# Power_Supply.net
KiCad netlist of a schematic drawn in Altium Designer
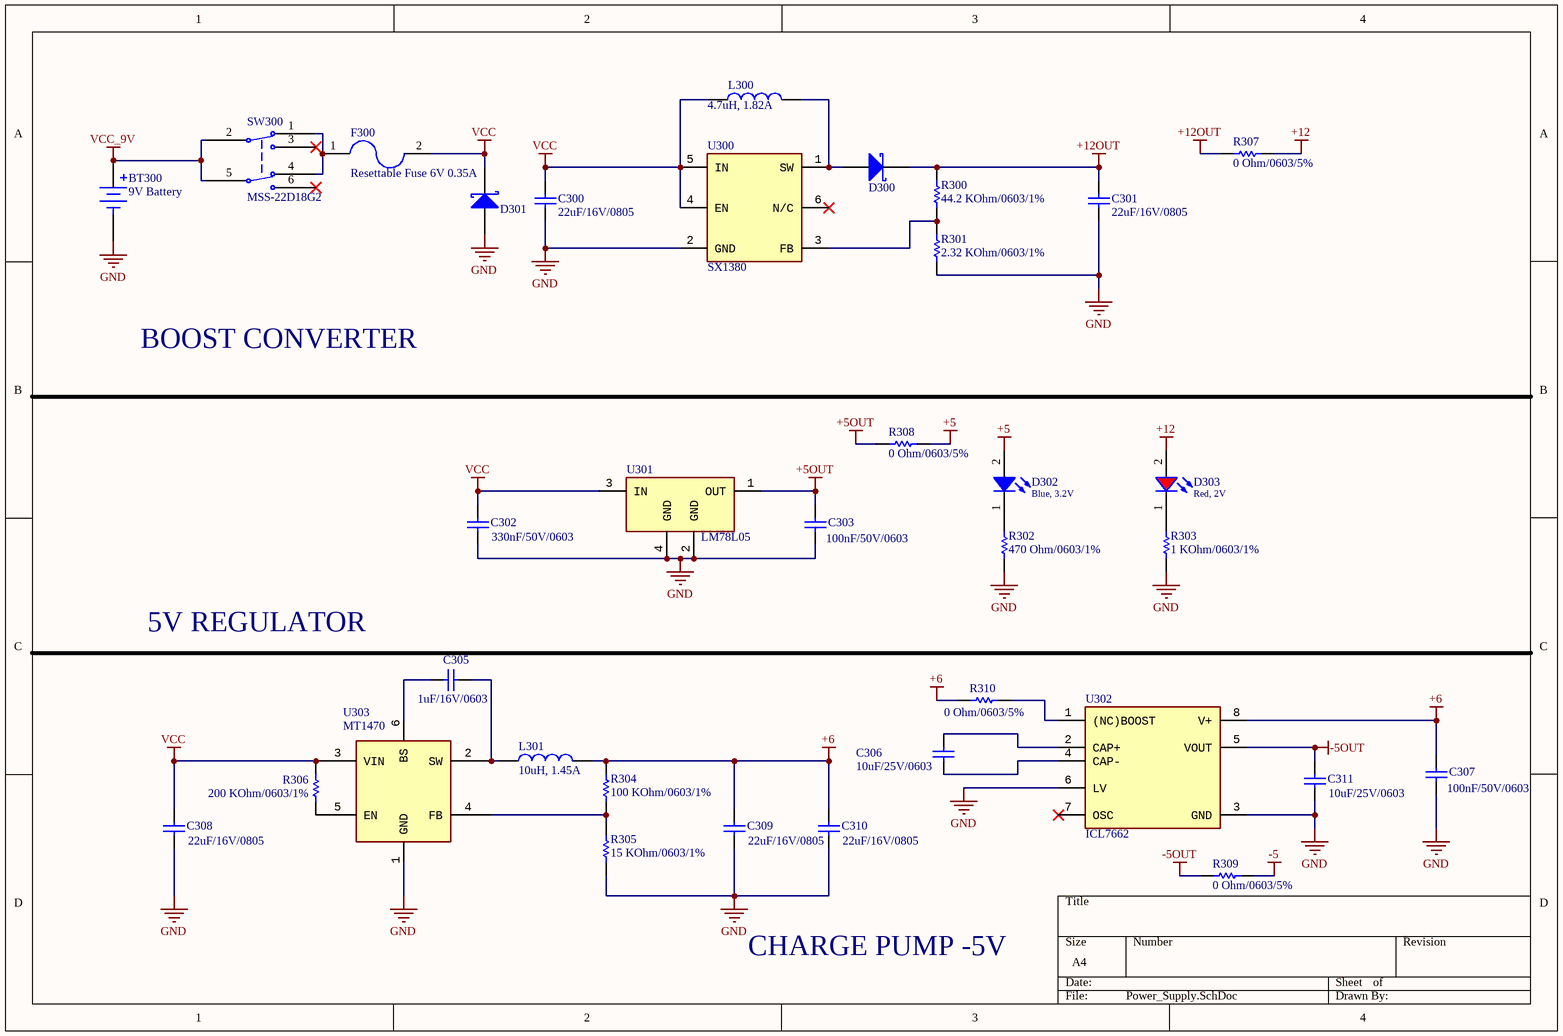
[diagram p0: Power_Supply.SchDoc]

(export (version "E")
  (design (tool "Eeschema 10.0.6"))
  (components
    (comp (ref "BT300")
      (value "9V Battery")
      (footprint "BAT_BC9VPC")
      (description "Battery Holder 1 Cells 9V Size Plastic Tray")
      (fields (field (name "MF") "MPD (Memory Protection Devices)") (field (name "MP") "BC9VPC"))
      (libsource (lib "Giang's Libs") (part "BC9VPC"))
    )
    (comp (ref "C300")
      (value "22uF/16V/0805")
      (footprint "CAP-SM-0805")
      (description "Capacitor")
      (fields (field (name "Comment") "Cap Non-Pol SMD"))
      (libsource (lib "PIF_Library") (part "Cap Non-Pol SMD"))
    )
    (comp (ref "C301")
      (value "22uF/16V/0805")
      (footprint "CAP-SM-0805")
      (description "Capacitor")
      (fields (field (name "Comment") "Cap Non-Pol SMD"))
      (libsource (lib "PIF_Library") (part "Cap Non-Pol SMD"))
    )
    (comp (ref "C302")
      (value "330nF/50V/0603")
      (footprint "WCAP-CSGP_0603_H=0.8mm_Reflow")
      (description "WCAP-CSGP Multilayer Ceramic Chip Capacitor, General Purpose, size 0603, X7R, 330nF, 50V")
      (fields
        (field (name "MANUFACTURER PART NUMBER") "885012206121")
        (field (name "MANUFACTURER") "Wurth Elektronik")
      )
      (libsource (lib "Altium_WCAP-CSGP (rev20a)") (part "885012206121"))
    )
    (comp (ref "C303")
      (value "100nF/50V/0603")
      (footprint "WCAP-CSGP_0603_H=0.8mm_Reflow")
      (description "WCAP-CSGP Multilayer Ceramic Chip Capacitor, General Purpose, size 0603, X7R, 100nF, 25V")
      (fields
        (field (name "MANUFACTURER PART NUMBER") "885012206071")
        (field (name "MANUFACTURER") "Wurth Elektronik")
      )
      (libsource (lib "Altium_WCAP-CSGP (rev20a)") (part "885012206071"))
    )
    (comp (ref "C305")
      (value "1uF/16V/0603")
      (footprint "WCAP-CSGP_0603_H=0.8mm_Reflow")
      (description "WCAP-CSGP Multilayer Ceramic Chip Capacitor, General Purpose, size 0603, X5R, 1uF, 16V")
      (fields
        (field (name "MANUFACTURER PART NUMBER") "885012106017")
        (field (name "MANUFACTURER") "Wurth Elektronik")
      )
      (libsource (lib "Altium_WCAP-CSGP (rev20a)") (part "885012106017"))
    )
    (comp (ref "C306")
      (value "10uF/25V/0603")
      (footprint "WCAP-CSGP_0603_H=0.8mm_Reflow")
      (description "WCAP-CSGP Multilayer Ceramic Chip Capacitor, General Purpose, size 0603, X5R, 10uF, 6.3V")
      (fields
        (field (name "MANUFACTURER PART NUMBER") "885012106006")
        (field (name "MANUFACTURER") "Wurth Elektronik")
      )
      (libsource (lib "Altium_WCAP-CSGP (rev20a)") (part "885012106006"))
    )
    (comp (ref "C307")
      (value "100nF/50V/0603")
      (footprint "WCAP-CSGP_0603_H=0.8mm_Reflow")
      (description "WCAP-CSGP Multilayer Ceramic Chip Capacitor, General Purpose, size 0603, X7R, 100nF, 25V")
      (fields
        (field (name "MANUFACTURER PART NUMBER") "885012206071")
        (field (name "MANUFACTURER") "Wurth Elektronik")
      )
      (libsource (lib "Altium_WCAP-CSGP (rev20a)") (part "885012206071"))
    )
    (comp (ref "C308")
      (value "22uF/16V/0805")
      (footprint "WCAP-CSGP_0805_H=1.25mm")
      (description "WCAP-CSGP Multilayer Ceramic Chip Capacitor, General Purpose, size 0805, X5R, 22uF, 10V")
      (fields
        (field (name "MANUFACTURER PART NUMBER") "885012107011")
        (field (name "MANUFACTURER") "Wurth Elektronik")
      )
      (libsource (lib "Altium_WCAP-CSGP (rev20a)") (part "885012107011"))
    )
    (comp (ref "C309")
      (value "22uF/16V/0805")
      (footprint "WCAP-CSGP_0805_H=1.25mm")
      (description "WCAP-CSGP Multilayer Ceramic Chip Capacitor, General Purpose, size 0805, X5R, 22uF, 10V")
      (fields
        (field (name "MANUFACTURER PART NUMBER") "885012107011")
        (field (name "MANUFACTURER") "Wurth Elektronik")
      )
      (libsource (lib "Altium_WCAP-CSGP (rev20a)") (part "885012107011"))
    )
    (comp (ref "C310")
      (value "22uF/16V/0805")
      (footprint "WCAP-CSGP_0805_H=1.25mm")
      (description "WCAP-CSGP Multilayer Ceramic Chip Capacitor, General Purpose, size 0805, X5R, 22uF, 10V")
      (fields
        (field (name "MANUFACTURER PART NUMBER") "885012107011")
        (field (name "MANUFACTURER") "Wurth Elektronik")
      )
      (libsource (lib "Altium_WCAP-CSGP (rev20a)") (part "885012107011"))
    )
    (comp (ref "C311")
      (value "10uF/25V/0603")
      (footprint "WCAP-CSGP_0603_H=0.8mm_Reflow")
      (description "WCAP-CSGP Multilayer Ceramic Chip Capacitor, General Purpose, size 0603, X5R, 10uF, 6.3V")
      (fields
        (field (name "MANUFACTURER PART NUMBER") "885012106006")
        (field (name "MANUFACTURER") "Wurth Elektronik")
      )
      (libsource (lib "Altium_WCAP-CSGP (rev20a)") (part "885012106006"))
    )
    (comp (ref "D300")
      (value "D Schottky")
      (footprint "SS34")
      (description "Schottky Diode")
      (fields (field (name "PUBLISHER") "Altium Limited"))
      (libsource (lib "PIF_Library") (part "D Schottky"))
    )
    (comp (ref "D301")
      (value "D Schottky")
      (footprint "SS34")
      (description "Schottky Diode")
      (fields (field (name "PUBLISHER") "Altium Limited"))
      (libsource (lib "PIF_Library") (part "D Schottky"))
    )
    (comp (ref "D302")
      (value "Blue, 3.2V")
      (footprint "WL-SMCW_0603_H=0.7mm")
      (description "WL-SMCW SMT Mono-color Chip LED Waterclear, size 0603, Blue, 3.2V, 140deg")
      (fields (field (name "PART NUMBER") "150060BS75000") (field (name "PUBLISHER") "Wurth Elektronik"))
      (libsource (lib "Altium_WL-SMCW (rev20a)") (part "150060BS75000"))
    )
    (comp (ref "D303")
      (value "Red, 2V")
      (footprint "WL-SMCW_0603_H=0.7mm")
      (description "WL-SMCW SMT Mono-color Chip LED Waterclear, size 0603, Red, 2V, 140deg")
      (fields (field (name "PART NUMBER") "150060RS75000") (field (name "PUBLISHER") "Wurth Elektronik"))
      (libsource (lib "Altium_WL-SMCW (rev20a)") (part "150060RS75000"))
    )
    (comp (ref "F300")
      (value "Resettable Fuse 6V 0.35A")
      (footprint "FUSE1206")
      (description "Polymeric PTC Resettable Fuse 6V 350mA Ih Surface Mount 1206 _3216 Metric_, Concave")
      (fields (field (name "MF") "Littelfuse Inc.") (field (name "MP") "1206L035YR"))
      (libsource (lib "Giang's Libs") (part "RESETTABLE FUSE 1206"))
    )
    (comp (ref "L300")
      (value "4.7uH, 1.82A")
      (footprint "WE-PD2A_4532")
      (description "WE-PD2A SMT Power Inductor, size 4532, 4.7uH, 1.82A")
      (fields
        (field (name "MANUFACTURER PART NUMBER") "784773047")
        (field (name "MANUFACTURER") "Wurth Elektronik")
      )
      (libsource (lib "Altium_WE-PD2A (rev20a)") (part "784773047"))
    )
    (comp (ref "L301")
      (value "10uH, 1.45A")
      (footprint "WE-PD2A_4532")
      (description "WE-PD2A SMT Power Inductor, size 4532, 10uH, 1.45A")
      (fields
        (field (name "MANUFACTURER PART NUMBER") "78477310")
        (field (name "MANUFACTURER") "Wurth Elektronik")
      )
      (libsource (lib "Altium_WE-PD2A (rev20a)") (part "78477310"))
    )
    (comp (ref "R300")
      (value "44.2 KOhm/0603/1%")
      (footprint "R0603")
      (description "Code (4422, 63C), 1/10W 1%")
      (fields (field (name "Comment") "Resistor 44.2 KOhm 0603 1%"))
      (libsource (lib "Giang_Resistor") (part "Resistor 44.2 KOhm 0603 1%"))
    )
    (comp (ref "R301")
      (value "2.32 KOhm/0603/1%")
      (footprint "R0603")
      (description "Code (2321, 36B), 1/10W")
      (fields (field (name "Comment") "Resistor 2.32 KOhm 0603 1%"))
      (libsource (lib "Giang_Resistor") (part "Resistor 2.32 KOhm 0603 1%"))
    )
    (comp (ref "R302")
      (value "470 Ohm/0603/1%")
      (footprint "R0603")
      (description "Code 471, 1/10W")
      (fields (field (name "Comment") "Resistor 470 Ohm 0603 1%"))
      (libsource (lib "Giang_Resistor") (part "Resistor 470 Ohm 0603 1%"))
    )
    (comp (ref "R303")
      (value "1 KOhm/0603/1%")
      (footprint "R0603")
      (description "Code 102, 1/10W")
      (fields (field (name "Comment") "Resistor 1 KOhm 0603 1%"))
      (libsource (lib "Giang_Resistor") (part "Resistor 1 KOhm 0603 1%"))
    )
    (comp (ref "R304")
      (value "100 KOhm/0603/1%")
      (footprint "R0603")
      (description "Code 104, 1/10W")
      (fields (field (name "Comment") "Resistor 100 KOhm 0603 1%"))
      (libsource (lib "Giang_Resistor") (part "Resistor 100 KOhm 0603 1%"))
    )
    (comp (ref "R305")
      (value "15 KOhm/0603/1%")
      (footprint "R0603")
      (description "Code 153, 1/10W")
      (fields (field (name "Comment") "Resistor 15 KOhm 0603 1%"))
      (libsource (lib "Giang_Resistor") (part "Resistor 15 KOhm 0603 1%"))
    )
    (comp (ref "R306")
      (value "200 KOhm/0603/1%")
      (footprint "R0603")
      (description "Code 2003, 1/10W")
      (fields (field (name "Comment") "Resistor 200 KOhm 0603 5%"))
      (libsource (lib "Giang_Resistor") (part "Resistor 200 KOhm 0603 5%"))
    )
    (comp (ref "R307")
      (value "0 Ohm/0603/5%")
      (footprint "R0603")
      (description "Code 0R, 1/10W")
      (fields (field (name "Comment") "Resistor 0 Ohm 0603 5%"))
      (libsource (lib "Giang_Resistor") (part "Resistor 0 Ohm 0603 5%"))
    )
    (comp (ref "R308")
      (value "0 Ohm/0603/5%")
      (footprint "R0603")
      (description "Code 0R, 1/10W")
      (fields (field (name "Comment") "Resistor 0 Ohm 0603 5%"))
      (libsource (lib "Giang_Resistor") (part "Resistor 0 Ohm 0603 5%"))
    )
    (comp (ref "R309")
      (value "0 Ohm/0603/5%")
      (footprint "R0603")
      (description "Code 0R, 1/10W")
      (fields (field (name "Comment") "Resistor 0 Ohm 0603 5%"))
      (libsource (lib "Giang_Resistor") (part "Resistor 0 Ohm 0603 5%"))
    )
    (comp (ref "R310")
      (value "0 Ohm/0603/5%")
      (footprint "R0603")
      (description "Code 0R, 1/10W")
      (fields (field (name "Comment") "Resistor 0 Ohm 0603 5%"))
      (libsource (lib "Giang_Resistor") (part "Resistor 0 Ohm 0603 5%"))
    )
    (comp (ref "SW300")
      (value "MSS-22D18G2")
      (footprint "MSS-22D18G2")
      (description "Slide Switch")
      (libsource (lib "Giang's Libs") (part "Slide Switch"))
    )
    (comp (ref "U300")
      (value "SX1380")
      (footprint "SOT-23-6")
      (description "High Efficiency 1.2MHz 2A Step Up Converter")
      (fields (field (name "MF") "Semtech Corporation") (field (name "MP") "SX1308"))
      (libsource (lib "Giang's Libs") (part "SX1308"))
    )
    (comp (ref "U301")
      (value "LM78L05")
      (footprint "SOT-89")
      (description "IC REG LINEAR 5V 100MA SOT89-3")
      (fields (field (name "MP") "78L05") (field (name "MF") "Hottech Co"))
      (libsource (lib "Giang's Libs") (part "78L05"))
    )
    (comp (ref "U302")
      (value "ICL7662")
      (footprint "SOIC-8")
      (description "CMOS, Voltage Converters")
      (fields (field (name "MP") "ICL7662EBA+") (field (name "MF") "Analog Devices"))
      (libsource (lib "Giang's Libs") (part "ICL7662EBA+"))
    )
    (comp (ref "U303")
      (value "MT1470")
      (footprint "SOT-23-6")
      (description "2A, 4.5 - 18V Input, 500kHz Synchronous Step-Down Converter")
      (libsource (lib "Giang's Libs") (part "MT1470"))
    )
  )
  (nets
    (net (code "1") (name "+5") (class "Default")
      (node (ref "D302") (pin "2") (pinfunction "A_2") (pintype "passive"))
      (node (ref "R308") (pin "2") (pinfunction "2_2") (pintype "passive"))
    )
    (net (code "2") (name "+5OUT") (class "Default")
      (node (ref "C303") (pin "1") (pinfunction "1_1") (pintype "passive"))
      (node (ref "R308") (pin "1") (pinfunction "1_1") (pintype "passive"))
      (node (ref "U301") (pin "1") (pinfunction "OUT_1") (pintype "power_in"))
    )
    (net (code "3") (name "+6") (class "Default")
      (node (ref "C307") (pin "1") (pinfunction "1_1") (pintype "passive"))
      (node (ref "C309") (pin "2") (pinfunction "2_2") (pintype "passive"))
      (node (ref "C310") (pin "2") (pinfunction "2_2") (pintype "passive"))
      (node (ref "L301") (pin "2") (pinfunction "2_2") (pintype "passive"))
      (node (ref "R304") (pin "2") (pinfunction "2_2") (pintype "passive"))
      (node (ref "R310") (pin "1") (pinfunction "1_1") (pintype "passive"))
      (node (ref "U302") (pin "8") (pinfunction "V+_8") (pintype "passive"))
    )
    (net (code "4") (name "+12") (class "Default")
      (node (ref "D303") (pin "2") (pinfunction "A_2") (pintype "passive"))
      (node (ref "R307") (pin "2") (pinfunction "2_2") (pintype "passive"))
    )
    (net (code "5") (name "+12OUT") (class "Default")
      (node (ref "C301") (pin "2") (pinfunction "2_2") (pintype "passive"))
      (node (ref "D300") (pin "2") (pinfunction "K_2") (pintype "passive"))
      (node (ref "R300") (pin "2") (pinfunction "2_2") (pintype "passive"))
      (node (ref "R307") (pin "1") (pinfunction "1_1") (pintype "passive"))
    )
    (net (code "6") (name "-5") (class "Default")
      (node (ref "R309") (pin "2") (pinfunction "2_2") (pintype "passive"))
    )
    (net (code "7") (name "-5OUT") (class "Default")
      (node (ref "C311") (pin "2") (pinfunction "2_2") (pintype "passive"))
      (node (ref "R309") (pin "1") (pinfunction "1_1") (pintype "passive"))
      (node (ref "U302") (pin "5") (pinfunction "VOUT_5") (pintype "passive"))
    )
    (net (code "8") (name "GND") (class "Default")
      (node (ref "BT300") (pin "N") (pinfunction "NEG_N") (pintype "passive"))
      (node (ref "C300") (pin "1") (pinfunction "1_1") (pintype "passive"))
      (node (ref "C301") (pin "1") (pinfunction "1_1") (pintype "passive"))
      (node (ref "C302") (pin "1") (pinfunction "1_1") (pintype "passive"))
      (node (ref "C303") (pin "2") (pinfunction "2_2") (pintype "passive"))
      (node (ref "C307") (pin "2") (pinfunction "2_2") (pintype "passive"))
      (node (ref "C308") (pin "1") (pinfunction "1_1") (pintype "passive"))
      (node (ref "C309") (pin "1") (pinfunction "1_1") (pintype "passive"))
      (node (ref "C310") (pin "1") (pinfunction "1_1") (pintype "passive"))
      (node (ref "C311") (pin "1") (pinfunction "1_1") (pintype "passive"))
      (node (ref "D301") (pin "1") (pinfunction "A_1") (pintype "passive"))
      (node (ref "R301") (pin "1") (pinfunction "1_1") (pintype "passive"))
      (node (ref "R302") (pin "1") (pinfunction "1_1") (pintype "passive"))
      (node (ref "R303") (pin "1") (pinfunction "1_1") (pintype "passive"))
      (node (ref "R305") (pin "1") (pinfunction "1_1") (pintype "passive"))
      (node (ref "U300") (pin "2") (pinfunction "GND_2") (pintype "passive"))
      (node (ref "U301") (pin "2") (pinfunction "GND_2") (pintype "power_in"))
      (node (ref "U301") (pin "4") (pinfunction "GND_4") (pintype "power_in"))
      (node (ref "U302") (pin "3") (pinfunction "GND_3") (pintype "passive"))
      (node (ref "U302") (pin "6") (pinfunction "LV_6") (pintype "passive"))
      (node (ref "U303") (pin "1") (pinfunction "GND_1") (pintype "passive"))
    )
    (net (code "9") (name "Net-(D300-A)") (class "Default")
      (node (ref "D300") (pin "1") (pinfunction "A_1") (pintype "passive"))
      (node (ref "L300") (pin "2") (pinfunction "2_2") (pintype "passive"))
      (node (ref "U300") (pin "1") (pinfunction "SW_1") (pintype "passive"))
    )
    (net (code "10") (name "Net-(D302-K)") (class "Default")
      (node (ref "D302") (pin "1") (pinfunction "K_1") (pintype "passive"))
      (node (ref "R302") (pin "2") (pinfunction "2_2") (pintype "passive"))
    )
    (net (code "11") (name "Net-(D303-K)") (class "Default")
      (node (ref "D303") (pin "1") (pinfunction "K_1") (pintype "passive"))
      (node (ref "R303") (pin "2") (pinfunction "2_2") (pintype "passive"))
    )
    (net (code "12") (name "Net-(SW300-10)") (class "Default")
      (node (ref "F300") (pin "1") (pinfunction "1_1") (pintype "passive"))
      (node (ref "SW300") (pin "1") (pinfunction "10_1") (pintype "passive"))
      (node (ref "SW300") (pin "4") (pinfunction "12_4") (pintype "passive"))
    )
    (net (code "13") (name "Net-(U300-FB)") (class "Default")
      (node (ref "R300") (pin "1") (pinfunction "1_1") (pintype "passive"))
      (node (ref "R301") (pin "2") (pinfunction "2_2") (pintype "passive"))
      (node (ref "U300") (pin "3") (pinfunction "FB_3") (pintype "passive"))
    )
    (net (code "14") (name "Net-(U302-(NC)BOOST)") (class "Default")
      (node (ref "R310") (pin "2") (pinfunction "2_2") (pintype "passive"))
      (node (ref "U302") (pin "1") (pinfunction "(NC)BOOST_1") (pintype "passive"))
    )
    (net (code "15") (name "Net-(U302-CAP+)") (class "Default")
      (node (ref "C306") (pin "2") (pinfunction "2_2") (pintype "passive"))
      (node (ref "U302") (pin "2") (pinfunction "CAP+_2") (pintype "passive"))
    )
    (net (code "16") (name "Net-(U302-CAP-)") (class "Default")
      (node (ref "C306") (pin "1") (pinfunction "1_1") (pintype "passive"))
      (node (ref "U302") (pin "4") (pinfunction "CAP-_4") (pintype "passive"))
    )
    (net (code "17") (name "Net-(U303-BS)") (class "Default")
      (node (ref "C305") (pin "1") (pinfunction "1_1") (pintype "passive"))
      (node (ref "U303") (pin "6") (pinfunction "BS_6") (pintype "passive"))
    )
    (net (code "18") (name "Net-(U303-EN)") (class "Default")
      (node (ref "R306") (pin "1") (pinfunction "1_1") (pintype "passive"))
      (node (ref "U303") (pin "5") (pinfunction "EN_5") (pintype "passive"))
    )
    (net (code "19") (name "Net-(U303-FB)") (class "Default")
      (node (ref "R304") (pin "1") (pinfunction "1_1") (pintype "passive"))
      (node (ref "R305") (pin "2") (pinfunction "2_2") (pintype "passive"))
      (node (ref "U303") (pin "4") (pinfunction "FB_4") (pintype "passive"))
    )
    (net (code "20") (name "Net-(U303-SW)") (class "Default")
      (node (ref "C305") (pin "2") (pinfunction "2_2") (pintype "passive"))
      (node (ref "L301") (pin "1") (pinfunction "1_1") (pintype "passive"))
      (node (ref "U303") (pin "2") (pinfunction "SW_2") (pintype "passive"))
    )
    (net (code "21") (name "VCC") (class "Default")
      (node (ref "C300") (pin "2") (pinfunction "2_2") (pintype "passive"))
      (node (ref "C302") (pin "2") (pinfunction "2_2") (pintype "passive"))
      (node (ref "C308") (pin "2") (pinfunction "2_2") (pintype "passive"))
      (node (ref "D301") (pin "2") (pinfunction "K_2") (pintype "passive"))
      (node (ref "F300") (pin "2") (pinfunction "2_2") (pintype "passive"))
      (node (ref "L300") (pin "1") (pinfunction "1_1") (pintype "passive"))
      (node (ref "R306") (pin "2") (pinfunction "2_2") (pintype "passive"))
      (node (ref "U300") (pin "4") (pinfunction "EN_4") (pintype "passive"))
      (node (ref "U300") (pin "5") (pinfunction "IN_5") (pintype "passive"))
      (node (ref "U301") (pin "3") (pinfunction "IN_3") (pintype "power_in"))
      (node (ref "U303") (pin "3") (pinfunction "VIN_3") (pintype "passive"))
    )
    (net (code "22") (name "VCC_9V") (class "Default")
      (node (ref "BT300") (pin "P") (pinfunction "POS_P") (pintype "passive"))
      (node (ref "SW300") (pin "2") (pinfunction "11_2") (pintype "passive"))
      (node (ref "SW300") (pin "5") (pinfunction "14_5") (pintype "passive"))
    )
    (net (code "23") (name "unconnected-(SW300-13-Pad3)") (class "Default")
      (node (ref "SW300") (pin "3") (pinfunction "13_3") (pintype "passive+no_connect"))
    )
    (net (code "24") (name "unconnected-(SW300-15-Pad6)") (class "Default")
      (node (ref "SW300") (pin "6") (pinfunction "15_6") (pintype "passive+no_connect"))
    )
    (net (code "25") (name "unconnected-(U300-N{slash}C-Pad6)") (class "Default")
      (node (ref "U300") (pin "6") (pinfunction "N/C_6") (pintype "passive+no_connect"))
    )
    (net (code "26") (name "unconnected-(U302-OSC-Pad7)") (class "Default")
      (node (ref "U302") (pin "7") (pinfunction "OSC_7") (pintype "passive+no_connect"))
    )
  )
)
